# TPS61169_SEPIC_90_mA_LED_Driver_V2_0.net
KiCad netlist of a schematic drawn in Altium Designer
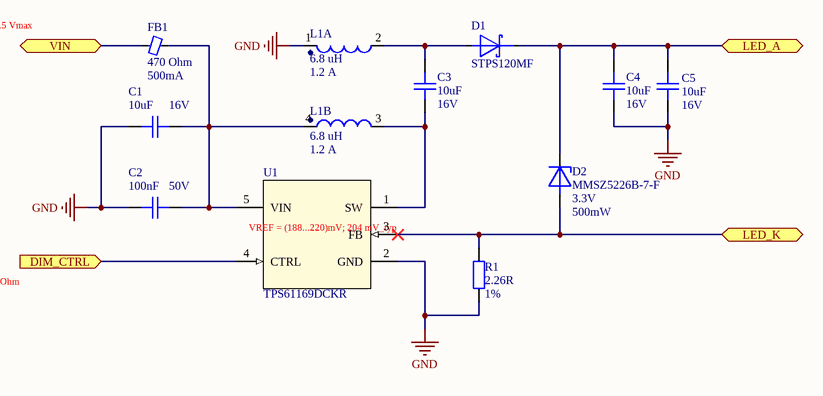
[diagram p0: TPS61169_SEPIC_90_mA_LED_Driver_V2.0.SchDoc]

(export (version "E")
  (design (tool "Eeschema 10.0.6"))
  (components
    (comp (ref "C1")
      (value "CAP CER 10UF 16V X5R 0603")
      (footprint "C0603")
      (description "10µF ±10% 16V Ceramic Capacitor X5R 0603 (1608 Metric)")
      (fields
        (field (name "MANUFACTURER") "Murata")
        (field (name "MANUFACTURER PART NUMBER") "GRM188R61C106KAALJ")
        (field (name "VOLTAGE RATING") "16V")
        (field (name "CAPACITANCE") "10uF")
      )
      (libsource (lib "capacitors_smd") (part "CAP CER 10UF 16V X5R 0603"))
    )
    (comp (ref "C2")
      (value "CAP CER 0.1UF 50V X7R 0402")
      (footprint "C0402")
      (description "0.1µF ±10% 50V Ceramic Capacitor X7R 0402 (1005 Metric)")
      (fields
        (field (name "MANUFACTURER") "TDK")
        (field (name "MANUFACTURER PART NUMBER") "CGA2B3X7R1H104K050BB")
        (field (name "CAPACITANCE") "100nF")
        (field (name "VOLTAGE") "50V")
      )
      (libsource (lib "capacitors_smd") (part "CAP CER 0.1UF 50V X7R 0402"))
    )
    (comp (ref "C3")
      (value "CAP CER 10UF 16V X7R 0805")
      (footprint "C0805")
      (description "10µF ±10% 16V Ceramic Capacitor X7R 0805 (2012 Metric)")
      (fields
        (field (name "MANUFACTURER") "Samsung")
        (field (name "MANUFACTURER PART NUMBER") "CL21B106KOQNNNG")
        (field (name "CAPACITANCE") "10uF")
        (field (name "VOLTAGE RATING") "16V")
      )
      (libsource (lib "capacitors_smd") (part "CAP CER 10UF 16V X7R 0805"))
    )
    (comp (ref "C4")
      (value "CAP CER 10UF 16V X5R 0603")
      (footprint "C0603")
      (description "10µF ±10% 16V Ceramic Capacitor X5R 0603 (1608 Metric)")
      (fields
        (field (name "MANUFACTURER") "Murata")
        (field (name "MANUFACTURER PART NUMBER") "GRM188R61C106KAALJ")
        (field (name "CAPACITANCE") "10uF")
        (field (name "VOLTAGE RATING") "16V")
      )
      (libsource (lib "capacitors_smd") (part "CAP CER 10UF 16V X5R 0603"))
    )
    (comp (ref "C5")
      (value "CAP CER 10UF 16V X5R 0603")
      (footprint "C0603")
      (description "10µF ±10% 16V Ceramic Capacitor X5R 0603 (1608 Metric)")
      (fields
        (field (name "MANUFACTURER") "Murata")
        (field (name "MANUFACTURER PART NUMBER") "GRM188R61C106KAALJ")
        (field (name "VOLTAGE RATING") "16V")
        (field (name "CAPACITANCE") "10uF")
      )
      (libsource (lib "capacitors_smd") (part "CAP CER 10UF 16V X5R 0603"))
    )
    (comp (ref "D1")
      (value "STPS120MF")
      (footprint "SODFL375X95-2N")
      (description "Diode Schottky 20V 1A Surface Mount STmite Flat")
      (fields (field (name "MANUFACTURER") "STMicroelectronics"))
      (libsource (lib "diodes_schottky") (part "DIODE SCHOTTKY 20V 1A STMITEFLAT"))
    )
    (comp (ref "D2")
      (value "MMSZ5226B-7-F")
      (footprint "SOD-123")
      (description "Zener Diode ±5% Surface Mount SOD-123")
      (fields
        (field (name "MANUFACTURER") "Diodes")
        (field (name "TOLERANCE") "5%")
        (field (name "WORKING VOLTAGE") "3.3V")
        (field (name "POWER RATING") "500mW")
      )
      (libsource (lib "diodes_zener") (part "DIODE ZENER 3.3V 500MW SOD123"))
    )
    (comp (ref "FB1")
      (value "FERRITE BEAD 470 OHM 0603 1LN")
      (footprint "L0603")
      (description "470 Ohms @ 100MHz 1  Ferrite Bead 0603 (1608 Metric) 500mA 210mOhm")
      (fields
        (field (name "MANUFACTURER") "Murata")
        (field (name "MANUFACTURER PART NUMBER") "BLM18EG471SN1D")
        (field (name "IMPEDANCE") "470 Ohm")
        (field (name "CURRENT RATING") "500mA")
      )
      (libsource (lib "ferrite_beads") (part "FERRITE BEAD 470 OHM 0603 1LN"))
    )
    (comp (ref "L1")
      (value "FIXED IND COUIPLED 6.8UH 1.2A 160 mOHM SMD")
      (footprint "IND_LPD5030")
      (description "6.8µH Shielded Coupled Inductors 1.2A 160mOhm Max 1919 (4.8x4.8 Metric)")
      (fields
        (field (name "MANUFACTURER") "Coilcraft")
        (field (name "MANUFACTURER PART NUMBER") "LPD5030-682MR")
        (field (name "INDUCTANCE") "6.8 uH")
        (field (name "MAXIMUM DC CURRENT") "1.2 A")
      )
      (libsource (lib "inductors_smd") (part "FIXED IND COUIPLED 6.8UH 1.2A 160 mOHM SMD"))
    )
    (comp (ref "R1")
      (value "RES SMD 2.26 OHM 1% 1/10W 0603")
      (footprint "R0603")
      (description "2.26 Ohms ±1% 0.1W, 1/10W Chip Resistor 0603 (1608 Metric) Automotive AEC-Q200 Thick Film")
      (fields
        (field (name "MANUFACTURER PART NUMBER") "CRCW06032R26FKEA")
        (field (name "MANUFACTURER") "Vishay Dale")
        (field (name "RESISTANCE") "2.26R")
        (field (name "TOLERANCE") "1%")
      )
      (libsource (lib "resistors_smd") (part "RES SMD 2.26 OHM 1% 1/10W 0603"))
    )
    (comp (ref "U1")
      (value "TPS61169DCKR")
      (footprint "DCK0005A_L")
      (description "LED Driver IC 1 Output DC DC Regulator Step-Up (Boost) PWM Dimming 1.8A (Switch) SC-70-5")
      (fields (field (name "MANUFACTURER") "Texas Instruments"))
      (libsource (lib "dcdc_converters") (part "IC TPS61169 WLED BACKLIGHT DRIVER SC70-5"))
    )
  )
  (nets
    (net (code "1") (name "/DIM_CTRL") (class "Default")
      (node (ref "U1") (pin "4") (pinfunction "CTRL_4") (pintype "input"))
    )
    (net (code "2") (name "/LED_A") (class "Default")
      (node (ref "C4") (pin "2") (pinfunction "2_2") (pintype "passive"))
      (node (ref "C5") (pin "1") (pinfunction "1_1") (pintype "passive"))
      (node (ref "D1") (pin "1") (pinfunction "K_1") (pintype "passive"))
      (node (ref "D2") (pin "1") (pinfunction "K_1") (pintype "passive"))
    )
    (net (code "3") (name "/LED_K") (class "Default")
      (node (ref "D2") (pin "2") (pinfunction "A_2") (pintype "passive"))
      (node (ref "R1") (pin "2") (pinfunction "2_2") (pintype "passive"))
      (node (ref "U1") (pin "3") (pinfunction "FB_3") (pintype "input"))
    )
    (net (code "4") (name "/VIN") (class "Default")
      (node (ref "FB1") (pin "1") (pinfunction "1_1") (pintype "passive"))
    )
    (net (code "5") (name "GND") (class "Default")
      (node (ref "C1") (pin "1") (pinfunction "1_1") (pintype "passive"))
      (node (ref "C2") (pin "2") (pinfunction "2_2") (pintype "passive"))
      (node (ref "C4") (pin "1") (pinfunction "1_1") (pintype "passive"))
      (node (ref "C5") (pin "2") (pinfunction "2_2") (pintype "passive"))
      (node (ref "L1") (pin "1") (pinfunction "1_1") (pintype "passive"))
      (node (ref "R1") (pin "1") (pinfunction "1_1") (pintype "passive"))
      (node (ref "U1") (pin "2") (pinfunction "GND_2") (pintype "power_in"))
    )
    (net (code "6") (name "Net-(D1-A)") (class "Default")
      (node (ref "C3") (pin "2") (pinfunction "2_2") (pintype "passive"))
      (node (ref "D1") (pin "2") (pinfunction "A_2") (pintype "passive"))
      (node (ref "L1") (pin "2") (pinfunction "2_2") (pintype "passive"))
    )
    (net (code "7") (name "Net-(U1-SW)") (class "Default")
      (node (ref "C3") (pin "1") (pinfunction "1_1") (pintype "passive"))
      (node (ref "L1") (pin "3") (pinfunction "3_3") (pintype "passive"))
      (node (ref "U1") (pin "1") (pinfunction "SW_1") (pintype "power_in"))
    )
    (net (code "8") (name "Net-(U1-VIN)") (class "Default")
      (node (ref "C1") (pin "2") (pinfunction "2_2") (pintype "passive"))
      (node (ref "C2") (pin "1") (pinfunction "1_1") (pintype "passive"))
      (node (ref "FB1") (pin "2") (pinfunction "2_2") (pintype "passive"))
      (node (ref "L1") (pin "4") (pinfunction "4_4") (pintype "passive"))
      (node (ref "U1") (pin "5") (pinfunction "VIN_5") (pintype "power_in"))
    )
  )
)
